# Anemometer.net
KiCad netlist of a schematic drawn in EAGLE
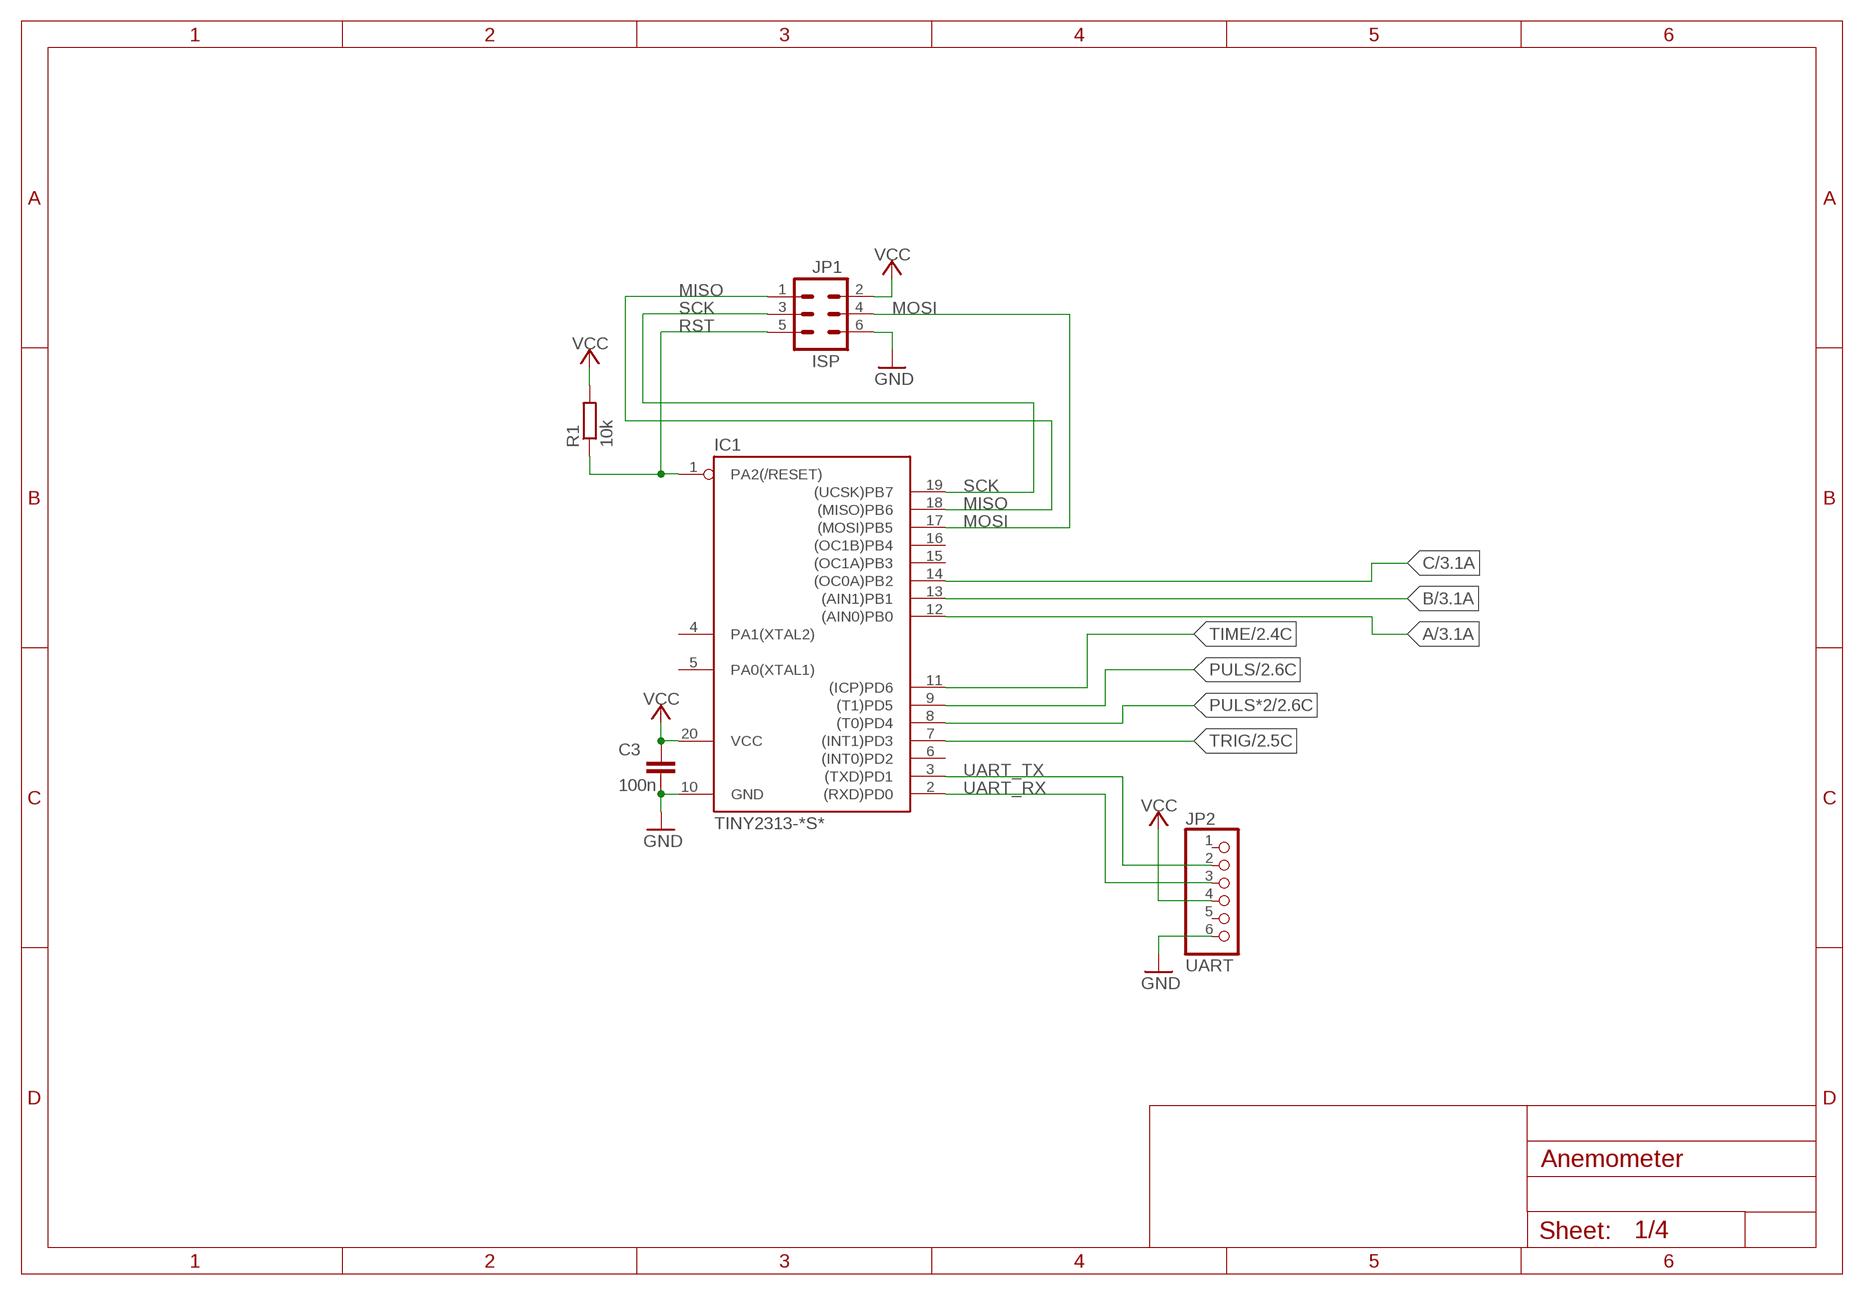
[diagram p0: schematic, sheet 1]
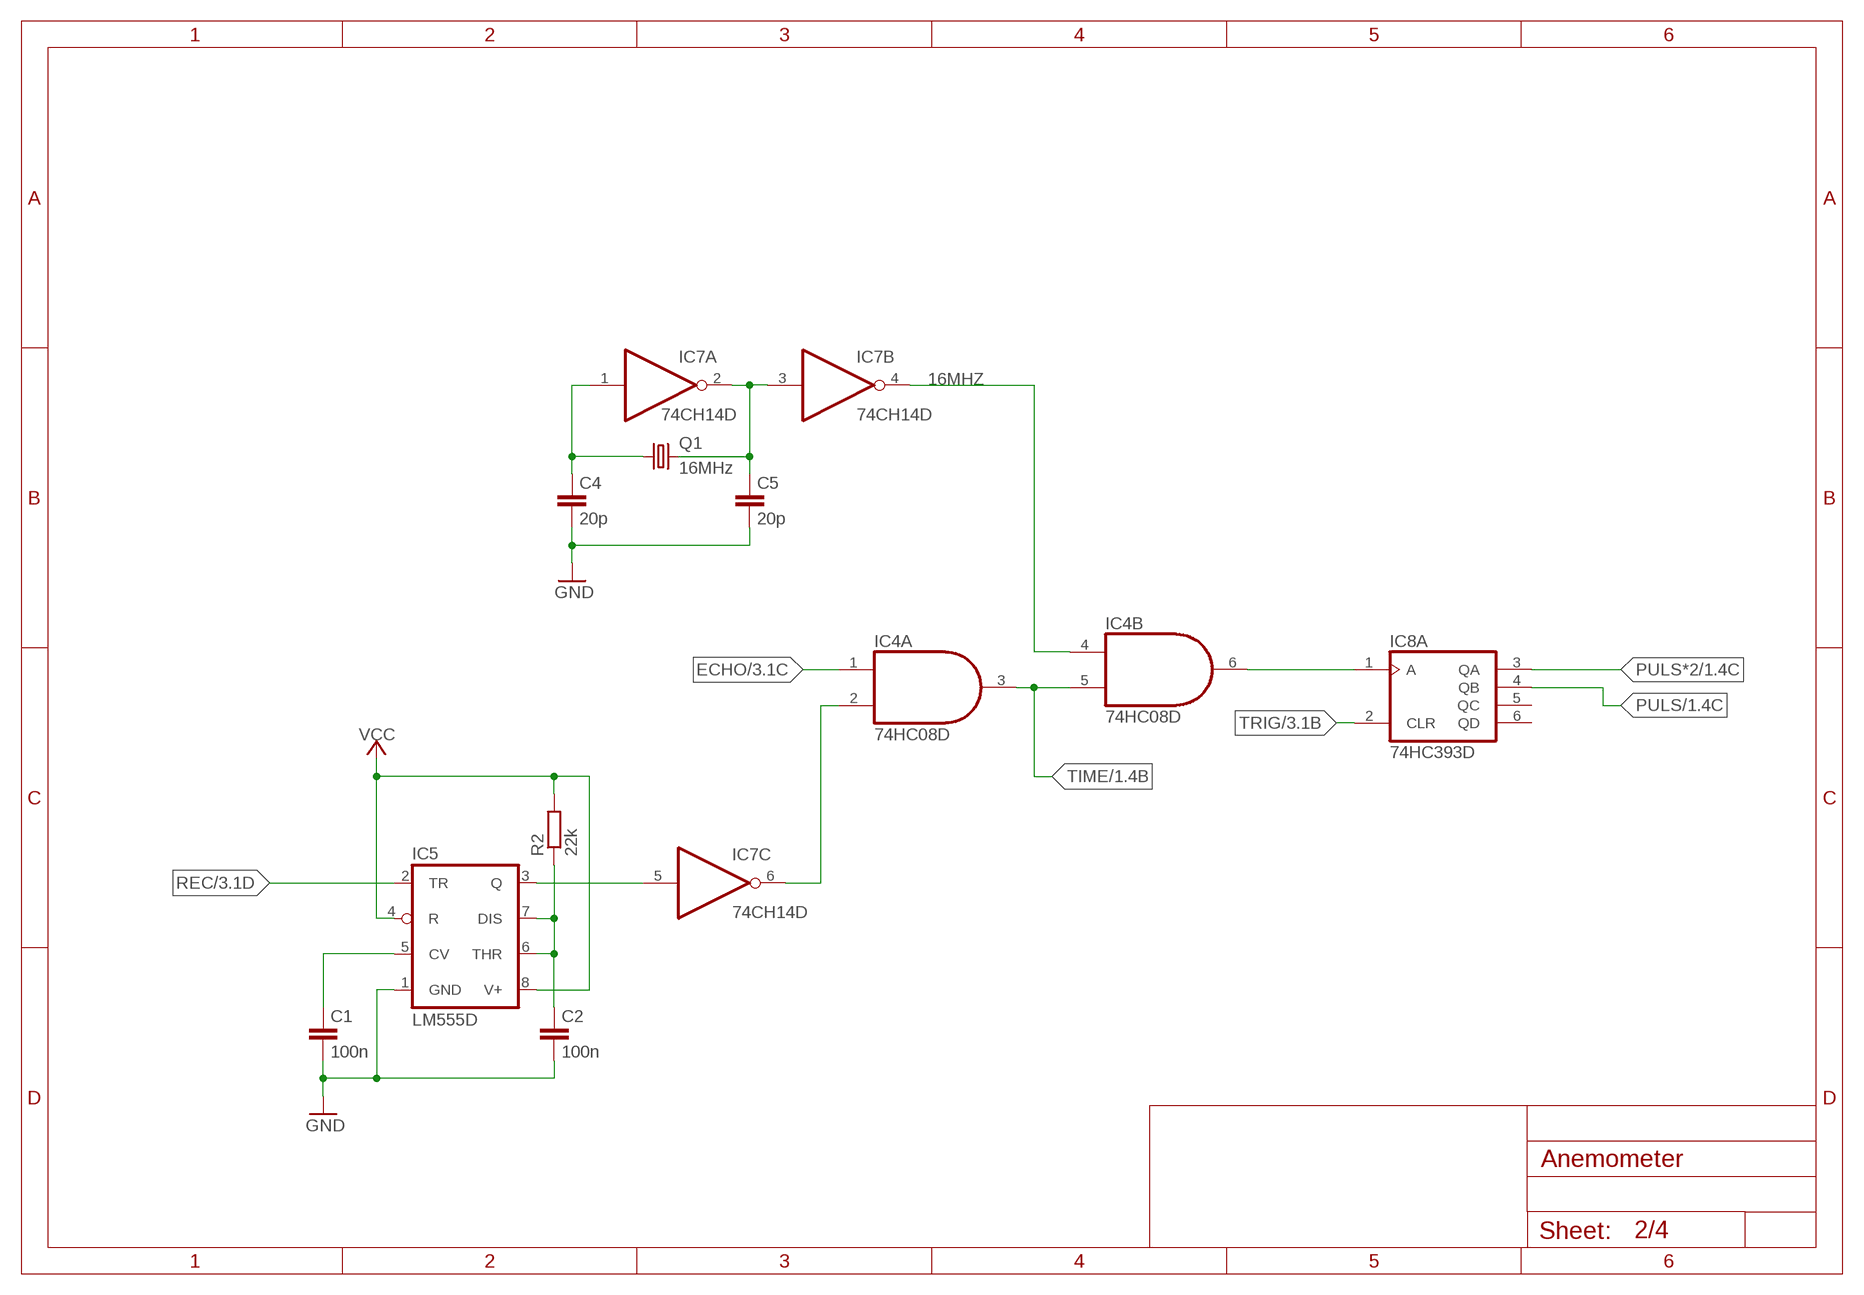
[diagram p1: schematic, sheet 2]
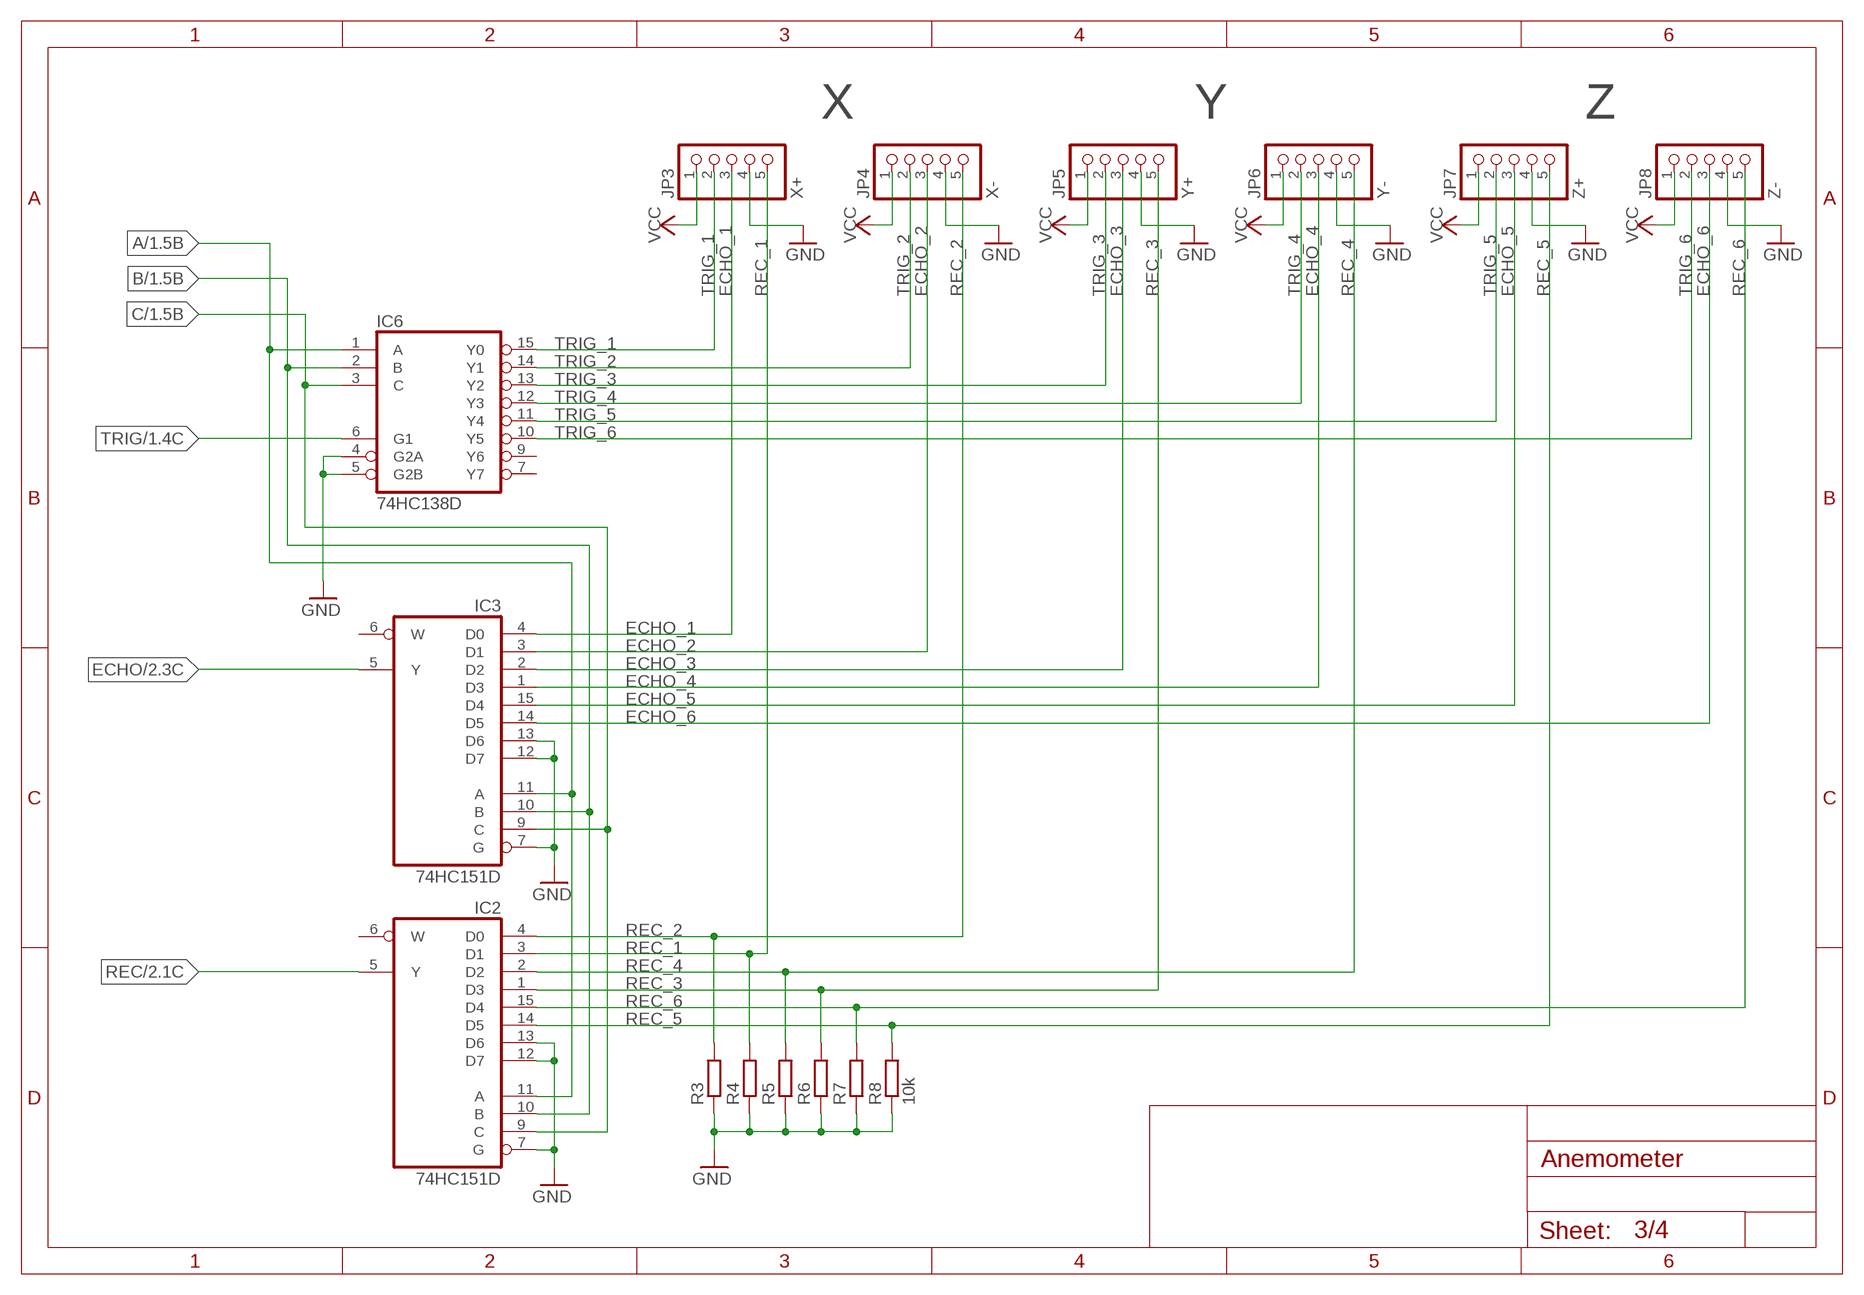
[diagram p2: schematic, sheet 3]
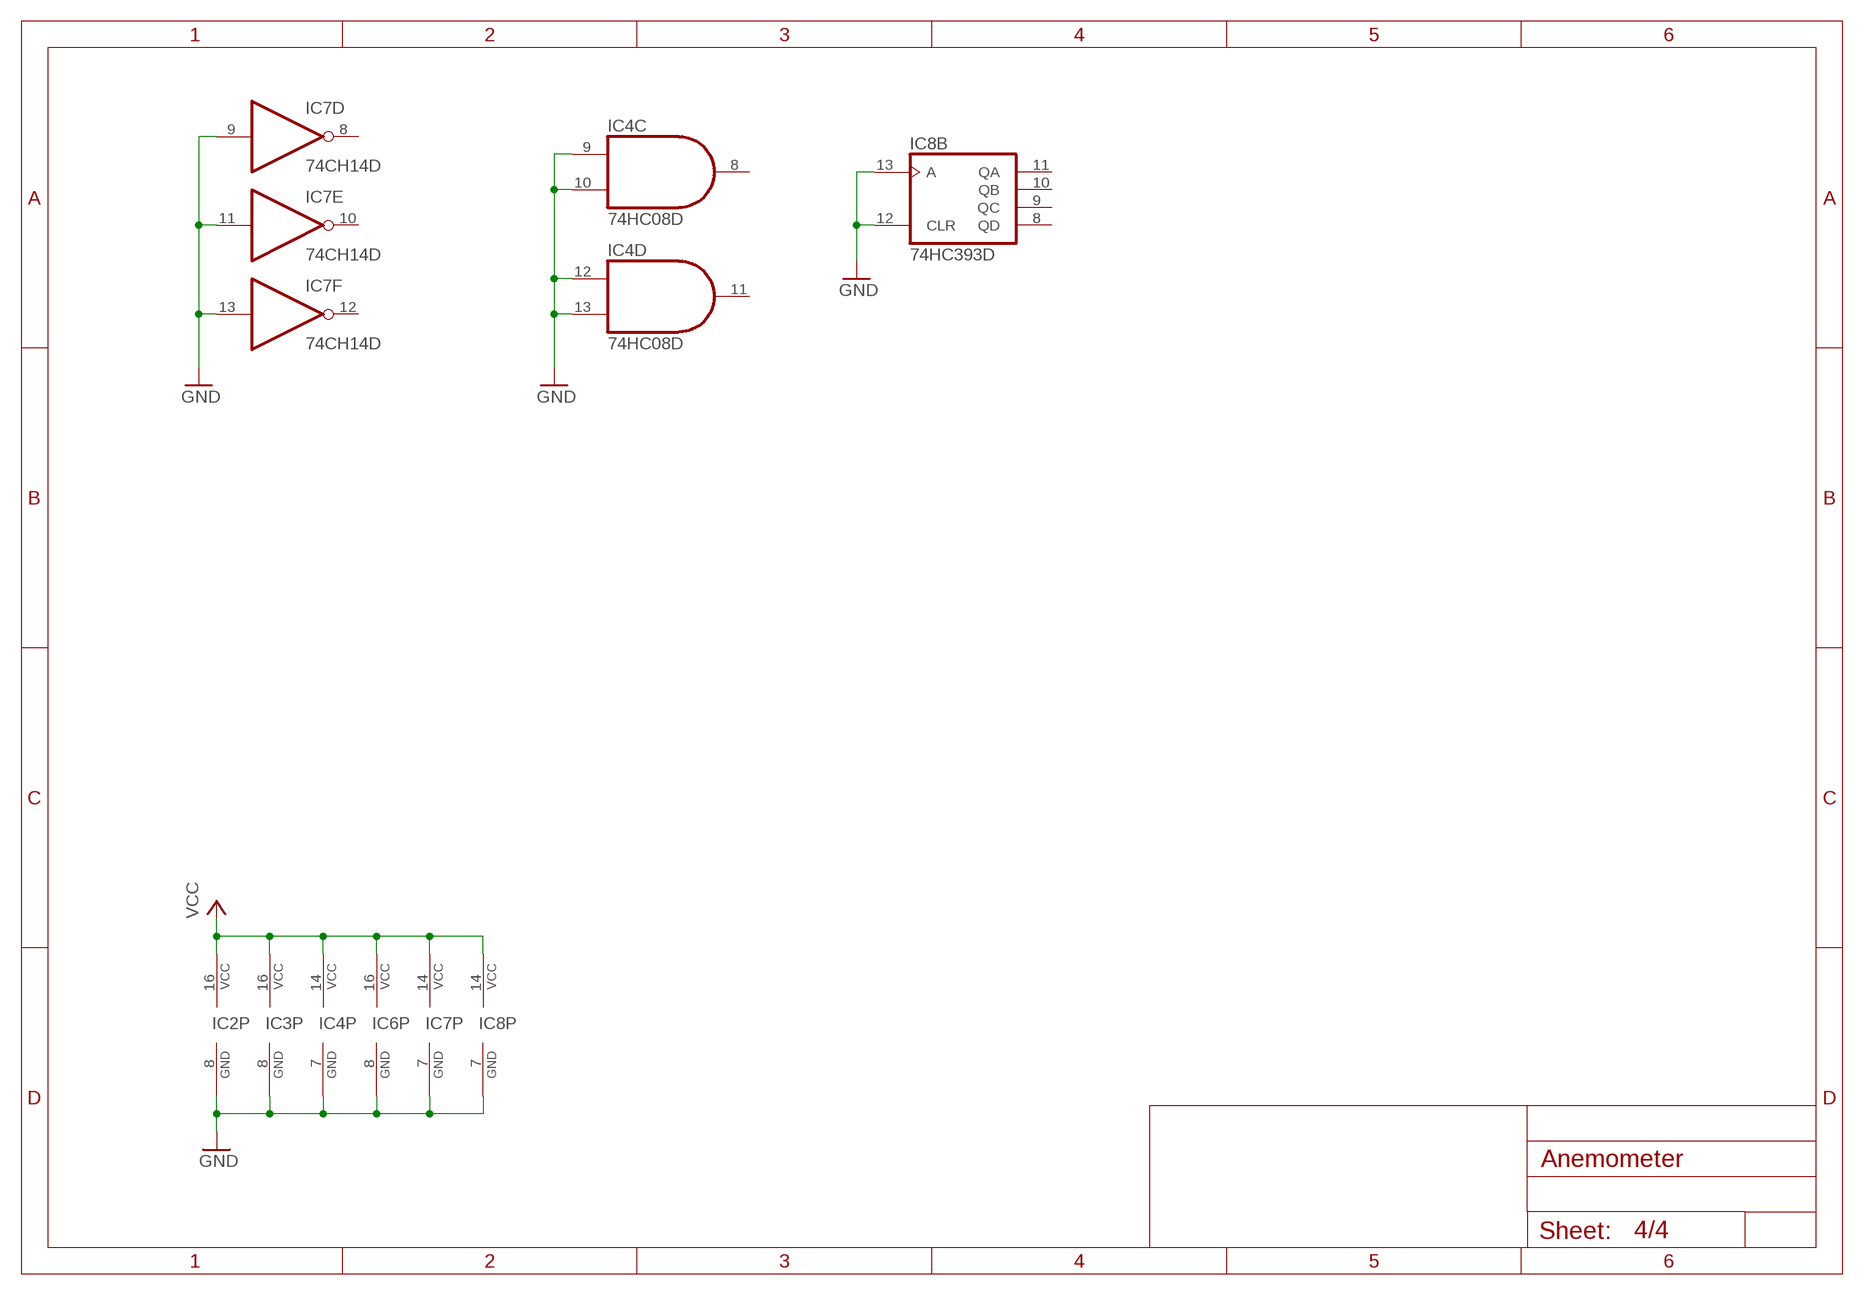
[diagram p3: schematic, sheet 4]

(export (version "E")
  (design (tool "Eeschema 10.0.6"))
  (components
    (comp (ref "C3")
      (value "100n")
      (footprint "eagle-import:C050-024X044")
      (libsource (lib "eagle-import") (part "C-EU050-024X044"))
    )
    (comp (ref "IC1")
      (value "TINY2313-*S*")
      (footprint "eagle-import:SO20L$")
      (libsource (lib "eagle-import") (part "TINY2313-S"))
    )
    (comp (ref "JP1")
      (value "ISP")
      (footprint "eagle-import:ML6")
      (libsource (lib "eagle-import") (part "ML6"))
    )
    (comp (ref "JP2")
      (value "UART")
      (footprint "eagle-import:1X06")
      (libsource (lib "eagle-import") (part "PINHD-1X6"))
    )
    (comp (ref "R1")
      (value "10k")
      (footprint "eagle-import:0207_10")
      (libsource (lib "eagle-import") (part "R-EU_0207/10"))
    )
    (comp (ref "IC2")
      (value "74HC151D")
      (footprint "eagle-import:SO16")
      (libsource (lib "eagle-import") (part "74151DLS"))
    )
    (comp (ref "IC3")
      (value "74HC151D")
      (footprint "eagle-import:SO16")
      (libsource (lib "eagle-import") (part "74151DLS"))
    )
    (comp (ref "IC4")
      (value "74HC08D")
      (footprint "eagle-import:SO14")
      (libsource (lib "eagle-import") (part "7408DALS"))
    )
    (comp (ref "IC6")
      (value "74HC138D")
      (footprint "eagle-import:SO16")
      (libsource (lib "eagle-import") (part "74138DLS"))
    )
    (comp (ref "IC7")
      (value "74CH14D")
      (footprint "eagle-import:SO14")
      (libsource (lib "eagle-import") (part "7404DALS"))
    )
    (comp (ref "IC8")
      (value "74HC393D")
      (footprint "eagle-import:SO14")
      (libsource (lib "eagle-import") (part "74393DLS"))
    )
    (comp (ref "C1")
      (value "100n")
      (footprint "eagle-import:C0805")
      (libsource (lib "eagle-import") (part "C-EUC0805"))
    )
    (comp (ref "C2")
      (value "100n")
      (footprint "eagle-import:C0805")
      (libsource (lib "eagle-import") (part "C-EUC0805"))
    )
    (comp (ref "C4")
      (value "20p")
      (footprint "eagle-import:C0805")
      (libsource (lib "eagle-import") (part "C-EUC0805"))
    )
    (comp (ref "C5")
      (value "20p")
      (footprint "eagle-import:C0805")
      (libsource (lib "eagle-import") (part "C-EUC0805"))
    )
    (comp (ref "IC5")
      (value "LM555D")
      (footprint "eagle-import:SO08")
      (libsource (lib "eagle-import") (part "555DLM"))
    )
    (comp (ref "Q1")
      (value "16MHz")
      (footprint "eagle-import:HC49UP")
      (libsource (lib "eagle-import") (part "CRYSTALHC49UP"))
    )
    (comp (ref "R2")
      (value "22k")
      (footprint "eagle-import:R0805")
      (libsource (lib "eagle-import") (part "R-EU_R0805"))
    )
    (comp (ref "JP3")
      (value "X+")
      (footprint "eagle-import:1X05")
      (libsource (lib "eagle-import") (part "PINHD-1X5"))
    )
    (comp (ref "JP4")
      (value "X-")
      (footprint "eagle-import:1X05")
      (libsource (lib "eagle-import") (part "PINHD-1X5"))
    )
    (comp (ref "JP5")
      (value "Y+")
      (footprint "eagle-import:1X05")
      (libsource (lib "eagle-import") (part "PINHD-1X5"))
    )
    (comp (ref "JP6")
      (value "Y-")
      (footprint "eagle-import:1X05")
      (libsource (lib "eagle-import") (part "PINHD-1X5"))
    )
    (comp (ref "JP7")
      (value "Z+")
      (footprint "eagle-import:1X05")
      (libsource (lib "eagle-import") (part "PINHD-1X5"))
    )
    (comp (ref "JP8")
      (value "Z-")
      (footprint "eagle-import:1X05")
      (libsource (lib "eagle-import") (part "PINHD-1X5"))
    )
    (comp (ref "R3")
      (value "10k")
      (footprint "eagle-import:R0805")
      (libsource (lib "eagle-import") (part "R-EU_R0805"))
    )
    (comp (ref "R4")
      (value "10k")
      (footprint "eagle-import:R0805")
      (libsource (lib "eagle-import") (part "R-EU_R0805"))
    )
    (comp (ref "R5")
      (value "10k")
      (footprint "eagle-import:R0805")
      (libsource (lib "eagle-import") (part "R-EU_R0805"))
    )
    (comp (ref "R6")
      (value "10k")
      (footprint "eagle-import:R0805")
      (libsource (lib "eagle-import") (part "R-EU_R0805"))
    )
    (comp (ref "R7")
      (value "10k")
      (footprint "eagle-import:R0805")
      (libsource (lib "eagle-import") (part "R-EU_R0805"))
    )
    (comp (ref "R8")
      (value "10k")
      (footprint "eagle-import:R0805")
      (libsource (lib "eagle-import") (part "R-EU_R0805"))
    )
  )
  (nets
    (net (code "1") (name "16MHZ") (class "Default")
      (node (ref "IC4") (pin "4") (pinfunction "I0_4") (pintype "input"))
      (node (ref "IC7") (pin "4") (pinfunction "O_4") (pintype "output"))
    )
    (net (code "2") (name "A") (class "Default")
      (node (ref "IC1") (pin "12") (pinfunction "(AIN0)PB0_12") (pintype "bidirectional"))
      (node (ref "IC2") (pin "11") (pinfunction "A_11") (pintype "input"))
      (node (ref "IC3") (pin "11") (pinfunction "A_11") (pintype "input"))
      (node (ref "IC6") (pin "1") (pinfunction "A_1") (pintype "input"))
    )
    (net (code "3") (name "B") (class "Default")
      (node (ref "IC1") (pin "13") (pinfunction "(AIN1)PB1_13") (pintype "bidirectional"))
      (node (ref "IC2") (pin "10") (pinfunction "B_10") (pintype "input"))
      (node (ref "IC3") (pin "10") (pinfunction "B_10") (pintype "input"))
      (node (ref "IC6") (pin "2") (pinfunction "B_2") (pintype "input"))
    )
    (net (code "4") (name "C") (class "Default")
      (node (ref "IC1") (pin "14") (pinfunction "(OC0A)PB2_14") (pintype "bidirectional"))
      (node (ref "IC2") (pin "9") (pinfunction "C_9") (pintype "input"))
      (node (ref "IC3") (pin "9") (pinfunction "C_9") (pintype "input"))
      (node (ref "IC6") (pin "3") (pinfunction "C_3") (pintype "input"))
    )
    (net (code "5") (name "ECHO") (class "Default")
      (node (ref "IC3") (pin "5") (pinfunction "Y_5") (pintype "output"))
      (node (ref "IC4") (pin "1") (pinfunction "I0_1") (pintype "input"))
    )
    (net (code "6") (name "ECHO_1") (class "Default")
      (node (ref "IC3") (pin "4") (pinfunction "D0_4") (pintype "input"))
      (node (ref "JP3") (pin "3") (pinfunction "3_3") (pintype "passive"))
    )
    (net (code "7") (name "ECHO_2") (class "Default")
      (node (ref "IC3") (pin "3") (pinfunction "D1_3") (pintype "input"))
      (node (ref "JP4") (pin "3") (pinfunction "3_3") (pintype "passive"))
    )
    (net (code "8") (name "ECHO_3") (class "Default")
      (node (ref "IC3") (pin "2") (pinfunction "D2_2") (pintype "input"))
      (node (ref "JP5") (pin "3") (pinfunction "3_3") (pintype "passive"))
    )
    (net (code "9") (name "ECHO_4") (class "Default")
      (node (ref "IC3") (pin "1") (pinfunction "D3_1") (pintype "input"))
      (node (ref "JP6") (pin "3") (pinfunction "3_3") (pintype "passive"))
    )
    (net (code "10") (name "ECHO_5") (class "Default")
      (node (ref "IC3") (pin "15") (pinfunction "D4_15") (pintype "input"))
      (node (ref "JP7") (pin "3") (pinfunction "3_3") (pintype "passive"))
    )
    (net (code "11") (name "ECHO_6") (class "Default")
      (node (ref "IC3") (pin "14") (pinfunction "D5_14") (pintype "input"))
      (node (ref "JP8") (pin "3") (pinfunction "3_3") (pintype "passive"))
    )
    (net (code "12") (name "GND") (class "Default")
      (node (ref "C1") (pin "2") (pinfunction "2_2") (pintype "passive"))
      (node (ref "C2") (pin "2") (pinfunction "2_2") (pintype "passive"))
      (node (ref "C3") (pin "2") (pinfunction "2_2") (pintype "passive"))
      (node (ref "C4") (pin "2") (pinfunction "2_2") (pintype "passive"))
      (node (ref "C5") (pin "2") (pinfunction "2_2") (pintype "passive"))
      (node (ref "IC1") (pin "10") (pinfunction "GND_10") (pintype "power_in"))
      (node (ref "IC2") (pin "12") (pinfunction "D7_12") (pintype "input"))
      (node (ref "IC2") (pin "13") (pinfunction "D6_13") (pintype "input"))
      (node (ref "IC2") (pin "7") (pinfunction "G_7") (pintype "input"))
      (node (ref "IC2") (pin "8") (pinfunction "GND_8") (pintype "power_in"))
      (node (ref "IC3") (pin "12") (pinfunction "D7_12") (pintype "input"))
      (node (ref "IC3") (pin "13") (pinfunction "D6_13") (pintype "input"))
      (node (ref "IC3") (pin "7") (pinfunction "G_7") (pintype "input"))
      (node (ref "IC3") (pin "8") (pinfunction "GND_8") (pintype "power_in"))
      (node (ref "IC4") (pin "10") (pinfunction "I1_10") (pintype "input"))
      (node (ref "IC4") (pin "12") (pinfunction "I0_12") (pintype "input"))
      (node (ref "IC4") (pin "13") (pinfunction "I1_13") (pintype "input"))
      (node (ref "IC4") (pin "7") (pinfunction "GND_7") (pintype "power_in"))
      (node (ref "IC4") (pin "9") (pinfunction "I0_9") (pintype "input"))
      (node (ref "IC5") (pin "1") (pinfunction "GND_1") (pintype "power_in"))
      (node (ref "IC6") (pin "4") (pinfunction "G2A_4") (pintype "input"))
      (node (ref "IC6") (pin "5") (pinfunction "G2B_5") (pintype "input"))
      (node (ref "IC6") (pin "8") (pinfunction "GND_8") (pintype "power_in"))
      (node (ref "IC7") (pin "11") (pinfunction "I_11") (pintype "input"))
      (node (ref "IC7") (pin "13") (pinfunction "I_13") (pintype "input"))
      (node (ref "IC7") (pin "7") (pinfunction "GND_7") (pintype "power_in"))
      (node (ref "IC7") (pin "9") (pinfunction "I_9") (pintype "input"))
      (node (ref "IC8") (pin "12") (pinfunction "CLR_12") (pintype "input"))
      (node (ref "IC8") (pin "13") (pinfunction "A_13") (pintype "input"))
      (node (ref "IC8") (pin "7") (pinfunction "GND_7") (pintype "power_in"))
      (node (ref "JP1") (pin "6") (pinfunction "6_6") (pintype "passive"))
      (node (ref "JP2") (pin "6") (pinfunction "6_6") (pintype "passive"))
      (node (ref "JP3") (pin "4") (pinfunction "4_4") (pintype "passive"))
      (node (ref "JP4") (pin "4") (pinfunction "4_4") (pintype "passive"))
      (node (ref "JP5") (pin "4") (pinfunction "4_4") (pintype "passive"))
      (node (ref "JP6") (pin "4") (pinfunction "4_4") (pintype "passive"))
      (node (ref "JP7") (pin "4") (pinfunction "4_4") (pintype "passive"))
      (node (ref "JP8") (pin "4") (pinfunction "4_4") (pintype "passive"))
      (node (ref "R3") (pin "1") (pinfunction "1_1") (pintype "passive"))
      (node (ref "R4") (pin "1") (pinfunction "1_1") (pintype "passive"))
      (node (ref "R5") (pin "1") (pinfunction "1_1") (pintype "passive"))
      (node (ref "R6") (pin "1") (pinfunction "1_1") (pintype "passive"))
      (node (ref "R7") (pin "1") (pinfunction "1_1") (pintype "passive"))
      (node (ref "R8") (pin "1") (pinfunction "1_1") (pintype "passive"))
    )
    (net (code "13") (name "MISO") (class "Default")
      (node (ref "IC1") (pin "18") (pinfunction "(MISO)PB6_18") (pintype "bidirectional"))
      (node (ref "JP1") (pin "1") (pinfunction "1_1") (pintype "passive"))
    )
    (net (code "14") (name "MOSI") (class "Default")
      (node (ref "IC1") (pin "17") (pinfunction "(MOSI)PB5_17") (pintype "bidirectional"))
      (node (ref "JP1") (pin "4") (pinfunction "4_4") (pintype "passive"))
    )
    (net (code "15") (name "Net-(IC4A-I1)") (class "Default")
      (node (ref "IC4") (pin "2") (pinfunction "I1_2") (pintype "input"))
      (node (ref "IC7") (pin "6") (pinfunction "O_6") (pintype "output"))
    )
    (net (code "16") (name "Net-(IC4B-O)") (class "Default")
      (node (ref "IC4") (pin "6") (pinfunction "O_6") (pintype "output"))
      (node (ref "IC8") (pin "1") (pinfunction "A_1") (pintype "input"))
    )
    (net (code "17") (name "Net-(IC5-CV)") (class "Default")
      (node (ref "C1") (pin "1") (pinfunction "1_1") (pintype "passive"))
      (node (ref "IC5") (pin "5") (pinfunction "CV_5") (pintype "input"))
    )
    (net (code "18") (name "Net-(IC5-DIS)") (class "Default")
      (node (ref "C2") (pin "1") (pinfunction "1_1") (pintype "passive"))
      (node (ref "IC5") (pin "6") (pinfunction "THR_6") (pintype "input"))
      (node (ref "IC5") (pin "7") (pinfunction "DIS_7") (pintype "input"))
      (node (ref "R2") (pin "1") (pinfunction "1_1") (pintype "passive"))
    )
    (net (code "19") (name "Net-(IC5-Q)") (class "Default")
      (node (ref "IC5") (pin "3") (pinfunction "Q_3") (pintype "output"))
      (node (ref "IC7") (pin "5") (pinfunction "I_5") (pintype "input"))
    )
    (net (code "20") (name "Net-(IC7A-I)") (class "Default")
      (node (ref "C4") (pin "1") (pinfunction "1_1") (pintype "passive"))
      (node (ref "IC7") (pin "1") (pinfunction "I_1") (pintype "input"))
      (node (ref "Q1") (pin "1") (pinfunction "1_1") (pintype "passive"))
    )
    (net (code "21") (name "Net-(IC7A-O)") (class "Default")
      (node (ref "C5") (pin "1") (pinfunction "1_1") (pintype "passive"))
      (node (ref "IC7") (pin "2") (pinfunction "O_2") (pintype "output"))
      (node (ref "IC7") (pin "3") (pinfunction "I_3") (pintype "input"))
      (node (ref "Q1") (pin "2") (pinfunction "2_2") (pintype "passive"))
    )
    (net (code "22") (name "PULS") (class "Default")
      (node (ref "IC1") (pin "9") (pinfunction "(T1)PD5_9") (pintype "bidirectional"))
      (node (ref "IC8") (pin "4") (pinfunction "QB_4") (pintype "output"))
    )
    (net (code "23") (name "PULS*2") (class "Default")
      (node (ref "IC1") (pin "8") (pinfunction "(T0)PD4_8") (pintype "bidirectional"))
      (node (ref "IC8") (pin "3") (pinfunction "QA_3") (pintype "output"))
    )
    (net (code "24") (name "REC") (class "Default")
      (node (ref "IC2") (pin "5") (pinfunction "Y_5") (pintype "output"))
      (node (ref "IC5") (pin "2") (pinfunction "TR_2") (pintype "input"))
    )
    (net (code "25") (name "REC_1") (class "Default")
      (node (ref "IC2") (pin "3") (pinfunction "D1_3") (pintype "input"))
      (node (ref "JP3") (pin "5") (pinfunction "5_5") (pintype "passive"))
      (node (ref "R4") (pin "2") (pinfunction "2_2") (pintype "passive"))
    )
    (net (code "26") (name "REC_2") (class "Default")
      (node (ref "IC2") (pin "4") (pinfunction "D0_4") (pintype "input"))
      (node (ref "JP4") (pin "5") (pinfunction "5_5") (pintype "passive"))
      (node (ref "R3") (pin "2") (pinfunction "2_2") (pintype "passive"))
    )
    (net (code "27") (name "REC_3") (class "Default")
      (node (ref "IC2") (pin "1") (pinfunction "D3_1") (pintype "input"))
      (node (ref "JP5") (pin "5") (pinfunction "5_5") (pintype "passive"))
      (node (ref "R6") (pin "2") (pinfunction "2_2") (pintype "passive"))
    )
    (net (code "28") (name "REC_4") (class "Default")
      (node (ref "IC2") (pin "2") (pinfunction "D2_2") (pintype "input"))
      (node (ref "JP6") (pin "5") (pinfunction "5_5") (pintype "passive"))
      (node (ref "R5") (pin "2") (pinfunction "2_2") (pintype "passive"))
    )
    (net (code "29") (name "REC_5") (class "Default")
      (node (ref "IC2") (pin "14") (pinfunction "D5_14") (pintype "input"))
      (node (ref "JP7") (pin "5") (pinfunction "5_5") (pintype "passive"))
      (node (ref "R8") (pin "2") (pinfunction "2_2") (pintype "passive"))
    )
    (net (code "30") (name "REC_6") (class "Default")
      (node (ref "IC2") (pin "15") (pinfunction "D4_15") (pintype "input"))
      (node (ref "JP8") (pin "5") (pinfunction "5_5") (pintype "passive"))
      (node (ref "R7") (pin "2") (pinfunction "2_2") (pintype "passive"))
    )
    (net (code "31") (name "RST") (class "Default")
      (node (ref "IC1") (pin "1") (pinfunction "PA2(/RESET)_1") (pintype "input"))
      (node (ref "JP1") (pin "5") (pinfunction "5_5") (pintype "passive"))
      (node (ref "R1") (pin "1") (pinfunction "1_1") (pintype "passive"))
    )
    (net (code "32") (name "SCK") (class "Default")
      (node (ref "IC1") (pin "19") (pinfunction "(UCSK)PB7_19") (pintype "bidirectional"))
      (node (ref "JP1") (pin "3") (pinfunction "3_3") (pintype "passive"))
    )
    (net (code "33") (name "TIME") (class "Default")
      (node (ref "IC1") (pin "11") (pinfunction "(ICP)PD6_11") (pintype "bidirectional"))
      (node (ref "IC4") (pin "3") (pinfunction "O_3") (pintype "output"))
      (node (ref "IC4") (pin "5") (pinfunction "I1_5") (pintype "input"))
    )
    (net (code "34") (name "TRIG") (class "Default")
      (node (ref "IC1") (pin "7") (pinfunction "(INT1)PD3_7") (pintype "bidirectional"))
      (node (ref "IC6") (pin "6") (pinfunction "G1_6") (pintype "input"))
      (node (ref "IC8") (pin "2") (pinfunction "CLR_2") (pintype "input"))
    )
    (net (code "35") (name "TRIG_1") (class "Default")
      (node (ref "IC6") (pin "15") (pinfunction "Y0_15") (pintype "output"))
      (node (ref "JP3") (pin "2") (pinfunction "2_2") (pintype "passive"))
    )
    (net (code "36") (name "TRIG_2") (class "Default")
      (node (ref "IC6") (pin "14") (pinfunction "Y1_14") (pintype "output"))
      (node (ref "JP4") (pin "2") (pinfunction "2_2") (pintype "passive"))
    )
    (net (code "37") (name "TRIG_3") (class "Default")
      (node (ref "IC6") (pin "13") (pinfunction "Y2_13") (pintype "output"))
      (node (ref "JP5") (pin "2") (pinfunction "2_2") (pintype "passive"))
    )
    (net (code "38") (name "TRIG_4") (class "Default")
      (node (ref "IC6") (pin "12") (pinfunction "Y3_12") (pintype "output"))
      (node (ref "JP6") (pin "2") (pinfunction "2_2") (pintype "passive"))
    )
    (net (code "39") (name "TRIG_5") (class "Default")
      (node (ref "IC6") (pin "11") (pinfunction "Y4_11") (pintype "output"))
      (node (ref "JP7") (pin "2") (pinfunction "2_2") (pintype "passive"))
    )
    (net (code "40") (name "TRIG_6") (class "Default")
      (node (ref "IC6") (pin "10") (pinfunction "Y5_10") (pintype "output"))
      (node (ref "JP8") (pin "2") (pinfunction "2_2") (pintype "passive"))
    )
    (net (code "41") (name "UART_RX") (class "Default")
      (node (ref "IC1") (pin "2") (pinfunction "(RXD)PD0_2") (pintype "bidirectional"))
      (node (ref "JP2") (pin "3") (pinfunction "3_3") (pintype "passive"))
    )
    (net (code "42") (name "UART_TX") (class "Default")
      (node (ref "IC1") (pin "3") (pinfunction "(TXD)PD1_3") (pintype "bidirectional"))
      (node (ref "JP2") (pin "2") (pinfunction "2_2") (pintype "passive"))
    )
    (net (code "43") (name "VCC") (class "Default")
      (node (ref "C3") (pin "1") (pinfunction "1_1") (pintype "passive"))
      (node (ref "IC1") (pin "20") (pinfunction "VCC_20") (pintype "power_in"))
      (node (ref "IC2") (pin "16") (pinfunction "VCC_16") (pintype "power_in"))
      (node (ref "IC3") (pin "16") (pinfunction "VCC_16") (pintype "power_in"))
      (node (ref "IC4") (pin "14") (pinfunction "VCC_14") (pintype "power_in"))
      (node (ref "IC5") (pin "4") (pinfunction "R_4") (pintype "input"))
      (node (ref "IC5") (pin "8") (pinfunction "V+_8") (pintype "power_in"))
      (node (ref "IC6") (pin "16") (pinfunction "VCC_16") (pintype "power_in"))
      (node (ref "IC7") (pin "14") (pinfunction "VCC_14") (pintype "power_in"))
      (node (ref "IC8") (pin "14") (pinfunction "VCC_14") (pintype "power_in"))
      (node (ref "JP1") (pin "2") (pinfunction "2_2") (pintype "passive"))
      (node (ref "JP2") (pin "4") (pinfunction "4_4") (pintype "passive"))
      (node (ref "JP3") (pin "1") (pinfunction "1_1") (pintype "passive"))
      (node (ref "JP4") (pin "1") (pinfunction "1_1") (pintype "passive"))
      (node (ref "JP5") (pin "1") (pinfunction "1_1") (pintype "passive"))
      (node (ref "JP6") (pin "1") (pinfunction "1_1") (pintype "passive"))
      (node (ref "JP7") (pin "1") (pinfunction "1_1") (pintype "passive"))
      (node (ref "JP8") (pin "1") (pinfunction "1_1") (pintype "passive"))
      (node (ref "R1") (pin "2") (pinfunction "2_2") (pintype "passive"))
      (node (ref "R2") (pin "2") (pinfunction "2_2") (pintype "passive"))
    )
    (net (code "44") (name "unconnected-(IC1-(INT0)PD2-Pad6)") (class "Default")
      (node (ref "IC1") (pin "6") (pinfunction "(INT0)PD2_6") (pintype "bidirectional"))
    )
    (net (code "45") (name "unconnected-(IC1-(OC1A)PB3-Pad15)") (class "Default")
      (node (ref "IC1") (pin "15") (pinfunction "(OC1A)PB3_15") (pintype "bidirectional"))
    )
    (net (code "46") (name "unconnected-(IC1-(OC1B)PB4-Pad16)") (class "Default")
      (node (ref "IC1") (pin "16") (pinfunction "(OC1B)PB4_16") (pintype "bidirectional"))
    )
    (net (code "47") (name "unconnected-(IC1-PA0(XTAL1)-Pad5)") (class "Default")
      (node (ref "IC1") (pin "5") (pinfunction "PA0(XTAL1)_5") (pintype "bidirectional"))
    )
    (net (code "48") (name "unconnected-(IC1-PA1(XTAL2)-Pad4)") (class "Default")
      (node (ref "IC1") (pin "4") (pinfunction "PA1(XTAL2)_4") (pintype "bidirectional"))
    )
    (net (code "49") (name "unconnected-(IC2A-W-Pad6)") (class "Default")
      (node (ref "IC2") (pin "6") (pinfunction "W_6") (pintype "output"))
    )
    (net (code "50") (name "unconnected-(IC3A-W-Pad6)") (class "Default")
      (node (ref "IC3") (pin "6") (pinfunction "W_6") (pintype "output"))
    )
    (net (code "51") (name "unconnected-(IC4C-O-Pad8)") (class "Default")
      (node (ref "IC4") (pin "8") (pinfunction "O_8") (pintype "output"))
    )
    (net (code "52") (name "unconnected-(IC4D-O-Pad11)") (class "Default")
      (node (ref "IC4") (pin "11") (pinfunction "O_11") (pintype "output"))
    )
    (net (code "53") (name "unconnected-(IC6A-Y6-Pad9)") (class "Default")
      (node (ref "IC6") (pin "9") (pinfunction "Y6_9") (pintype "output"))
    )
    (net (code "54") (name "unconnected-(IC6A-Y7-Pad7)") (class "Default")
      (node (ref "IC6") (pin "7") (pinfunction "Y7_7") (pintype "output"))
    )
    (net (code "55") (name "unconnected-(IC7D-O-Pad8)") (class "Default")
      (node (ref "IC7") (pin "8") (pinfunction "O_8") (pintype "output"))
    )
    (net (code "56") (name "unconnected-(IC7E-O-Pad10)") (class "Default")
      (node (ref "IC7") (pin "10") (pinfunction "O_10") (pintype "output"))
    )
    (net (code "57") (name "unconnected-(IC7F-O-Pad12)") (class "Default")
      (node (ref "IC7") (pin "12") (pinfunction "O_12") (pintype "output"))
    )
    (net (code "58") (name "unconnected-(IC8A-QC-Pad5)") (class "Default")
      (node (ref "IC8") (pin "5") (pinfunction "QC_5") (pintype "output"))
    )
    (net (code "59") (name "unconnected-(IC8A-QD-Pad6)") (class "Default")
      (node (ref "IC8") (pin "6") (pinfunction "QD_6") (pintype "output"))
    )
    (net (code "60") (name "unconnected-(IC8B-QA-Pad11)") (class "Default")
      (node (ref "IC8") (pin "11") (pinfunction "QA_11") (pintype "output"))
    )
    (net (code "61") (name "unconnected-(IC8B-QB-Pad10)") (class "Default")
      (node (ref "IC8") (pin "10") (pinfunction "QB_10") (pintype "output"))
    )
    (net (code "62") (name "unconnected-(IC8B-QC-Pad9)") (class "Default")
      (node (ref "IC8") (pin "9") (pinfunction "QC_9") (pintype "output"))
    )
    (net (code "63") (name "unconnected-(IC8B-QD-Pad8)") (class "Default")
      (node (ref "IC8") (pin "8") (pinfunction "QD_8") (pintype "output"))
    )
    (net (code "64") (name "unconnected-(JP2-Pad1)") (class "Default")
      (node (ref "JP2") (pin "1") (pinfunction "1_1") (pintype "passive"))
    )
    (net (code "65") (name "unconnected-(JP2-Pad5)") (class "Default")
      (node (ref "JP2") (pin "5") (pinfunction "5_5") (pintype "passive"))
    )
  )
)
